# ModuleXuLyAmThanhPT2314.net
KiCad netlist of a schematic drawn in Altium Designer
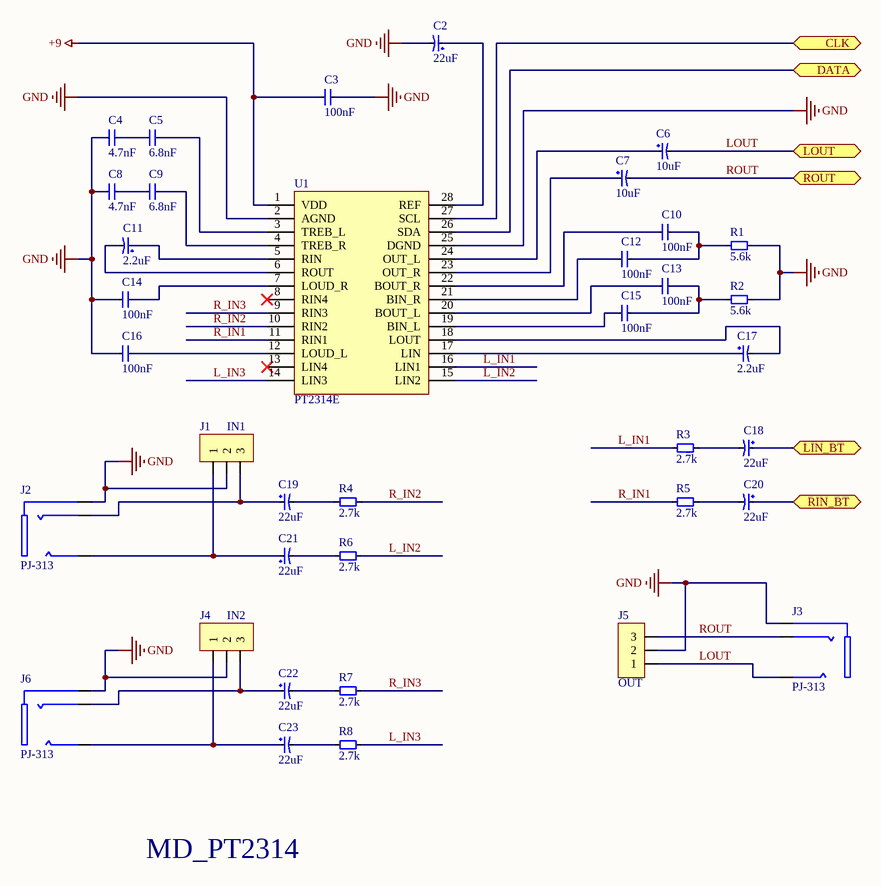
[diagram p0: ModuleXuLyAmThanhPT2314.SchDoc]

(export (version "E")
  (design (tool "Eeschema 10.0.6"))
  (components
    (comp (ref "C2")
      (value "22uF")
      (footprint "C-ELE-1.5-4X7MM")
      (description "Cac Loai Tu Hoa")
      (libsource (lib "phatvu1294_Lib") (part "CAP-ELE"))
    )
    (comp (ref "C3")
      (value "100nF")
      (footprint "C-0805")
      (description "Cac Loai Tu Khong Phan Cuc")
      (libsource (lib "phatvu1294_Lib") (part "CAP"))
    )
    (comp (ref "C4")
      (value "4.7nF")
      (footprint "C-0805")
      (description "Cac Loai Tu Khong Phan Cuc")
      (libsource (lib "phatvu1294_Lib") (part "CAP"))
    )
    (comp (ref "C5")
      (value "6.8nF")
      (footprint "C-0805")
      (description "Cac Loai Tu Khong Phan Cuc")
      (libsource (lib "phatvu1294_Lib") (part "CAP"))
    )
    (comp (ref "C6")
      (value "10uF")
      (footprint "C-ELE-1.5-4X7MM")
      (description "Cac Loai Tu Hoa")
      (libsource (lib "phatvu1294_Lib") (part "CAP-ELE"))
    )
    (comp (ref "C7")
      (value "10uF")
      (footprint "C-ELE-1.5-4X7MM")
      (description "Cac Loai Tu Hoa")
      (libsource (lib "phatvu1294_Lib") (part "CAP-ELE"))
    )
    (comp (ref "C8")
      (value "4.7nF")
      (footprint "C-0805")
      (description "Cac Loai Tu Khong Phan Cuc")
      (libsource (lib "phatvu1294_Lib") (part "CAP"))
    )
    (comp (ref "C9")
      (value "6.8nF")
      (footprint "C-0805")
      (description "Cac Loai Tu Khong Phan Cuc")
      (libsource (lib "phatvu1294_Lib") (part "CAP"))
    )
    (comp (ref "C10")
      (value "100nF")
      (footprint "C-0805")
      (description "Cac Loai Tu Khong Phan Cuc")
      (libsource (lib "phatvu1294_Lib") (part "CAP"))
    )
    (comp (ref "C11")
      (value "2.2uF")
      (footprint "C-ELE-1.5-4X7MM")
      (description "Cac Loai Tu Hoa")
      (libsource (lib "phatvu1294_Lib") (part "CAP-ELE"))
    )
    (comp (ref "C12")
      (value "100nF")
      (footprint "C-0805")
      (description "Cac Loai Tu Khong Phan Cuc")
      (libsource (lib "phatvu1294_Lib") (part "CAP"))
    )
    (comp (ref "C13")
      (value "100nF")
      (footprint "C-0805")
      (description "Cac Loai Tu Khong Phan Cuc")
      (libsource (lib "phatvu1294_Lib") (part "CAP"))
    )
    (comp (ref "C14")
      (value "100nF")
      (footprint "C-0805")
      (description "Cac Loai Tu Khong Phan Cuc")
      (libsource (lib "phatvu1294_Lib") (part "CAP"))
    )
    (comp (ref "C15")
      (value "100nF")
      (footprint "C-0805")
      (description "Cac Loai Tu Khong Phan Cuc")
      (libsource (lib "phatvu1294_Lib") (part "CAP"))
    )
    (comp (ref "C16")
      (value "100nF")
      (footprint "C-0805")
      (description "Cac Loai Tu Khong Phan Cuc")
      (libsource (lib "phatvu1294_Lib") (part "CAP"))
    )
    (comp (ref "C17")
      (value "2.2uF")
      (footprint "C-ELE-1.5-4X7MM")
      (description "Cac Loai Tu Hoa")
      (libsource (lib "phatvu1294_Lib") (part "CAP-ELE"))
    )
    (comp (ref "C18")
      (value "22uF")
      (footprint "C-ELE-1.5-4X7MM")
      (description "Cac Loai Tu Hoa")
      (libsource (lib "") (part "CAP-ELE_1"))
    )
    (comp (ref "C19")
      (value "22uF")
      (footprint "C-ELE-1.5-4X7MM")
      (description "Cac Loai Tu Hoa")
      (libsource (lib "phatvu1294_Lib") (part "CAP-ELE"))
    )
    (comp (ref "C20")
      (value "22uF")
      (footprint "C-ELE-1.5-4X7MM")
      (description "Cac Loai Tu Hoa")
      (libsource (lib "") (part "CAP-ELE_1"))
    )
    (comp (ref "C21")
      (value "22uF")
      (footprint "C-ELE-1.5-4X7MM")
      (description "Cac Loai Tu Hoa")
      (libsource (lib "") (part "CAP-ELE_1"))
    )
    (comp (ref "C22")
      (value "22uF")
      (footprint "C-ELE-1.5-4X7MM")
      (description "Cac Loai Tu Hoa")
      (libsource (lib "phatvu1294_Lib") (part "CAP-ELE"))
    )
    (comp (ref "C23")
      (value "22uF")
      (footprint "C-ELE-1.5-4X7MM")
      (description "Cac Loai Tu Hoa")
      (libsource (lib "phatvu1294_Lib") (part "CAP-ELE"))
    )
    (comp (ref "J1")
      (value "IN1")
      (footprint "XH1X3M-2.54")
      (description "Header 3 Chan XH 2.54mm")
      (libsource (lib "phatvu1294_Lib") (part "XH1X3-2.54"))
    )
    (comp (ref "J2")
      (value "PJ-313")
      (footprint "PJ-313")
      (description "Jack Ket Noi Audio 3.5MM")
      (libsource (lib "phatvu1294_Lib") (part "PJ-313"))
    )
    (comp (ref "J3")
      (value "PJ-313")
      (footprint "PJ-313")
      (description "Jack Ket Noi Audio 3.5MM")
      (libsource (lib "phatvu1294_Lib") (part "PJ-313"))
    )
    (comp (ref "J4")
      (value "IN2")
      (footprint "XH1X3M-2.54")
      (description "Header 3 Chan XH 2.54mm")
      (libsource (lib "phatvu1294_Lib") (part "XH1X3-2.54"))
    )
    (comp (ref "J5")
      (value "OUT")
      (footprint "XH1X3M-2.54")
      (description "Header 3 Chan XH 2.54mm")
      (libsource (lib "") (part "XH1X3-2.54_1"))
    )
    (comp (ref "J6")
      (value "PJ-313")
      (footprint "PJ-313")
      (description "Jack Ket Noi Audio 3.5MM")
      (libsource (lib "phatvu1294_Lib") (part "PJ-313"))
    )
    (comp (ref "R1")
      (value "5.6k")
      (footprint "R-0805")
      (description "Cac Loai Dien Tro")
      (libsource (lib "phatvu1294_Lib") (part "RES"))
    )
    (comp (ref "R2")
      (value "5.6k")
      (footprint "R-0805")
      (description "Cac Loai Dien Tro")
      (libsource (lib "phatvu1294_Lib") (part "RES"))
    )
    (comp (ref "R3")
      (value "2.7k")
      (footprint "R-0805")
      (description "Cac Loai Dien Tro")
      (libsource (lib "phatvu1294_Lib") (part "RES"))
    )
    (comp (ref "R4")
      (value "2.7k")
      (footprint "R-0805")
      (description "Cac Loai Dien Tro")
      (libsource (lib "phatvu1294_Lib") (part "RES"))
    )
    (comp (ref "R5")
      (value "2.7k")
      (footprint "R-0805")
      (description "Cac Loai Dien Tro")
      (libsource (lib "phatvu1294_Lib") (part "RES"))
    )
    (comp (ref "R6")
      (value "2.7k")
      (footprint "R-0805")
      (description "Cac Loai Dien Tro")
      (libsource (lib "phatvu1294_Lib") (part "RES"))
    )
    (comp (ref "R7")
      (value "2.7k")
      (footprint "R-0805")
      (description "Cac Loai Dien Tro")
      (libsource (lib "phatvu1294_Lib") (part "RES"))
    )
    (comp (ref "R8")
      (value "2.7k")
      (footprint "R-0805")
      (description "Cac Loai Dien Tro")
      (libsource (lib "phatvu1294_Lib") (part "RES"))
    )
    (comp (ref "U1")
      (value "PT2314E")
      (footprint "SO28W-1.27-300MIL")
      (description "IC Xu Ly Am Thanh So")
      (libsource (lib "phatvu1294_Lib") (part "PT2314E"))
    )
  )
  (nets
    (net (code "1") (name "+9") (class "Default")
      (node (ref "C3") (pin "1") (pinfunction "1_1") (pintype "passive"))
      (node (ref "U1") (pin "1") (pinfunction "VDD_1") (pintype "power_in"))
    )
    (net (code "2") (name "/CLK") (class "Default")
      (node (ref "U1") (pin "27") (pinfunction "SCL_27") (pintype "passive"))
    )
    (net (code "3") (name "/DATA") (class "Default")
      (node (ref "U1") (pin "26") (pinfunction "SDA_26") (pintype "passive"))
    )
    (net (code "4") (name "/LIN_BT") (class "Default")
      (node (ref "C18") (pin "1") (pinfunction "1_1") (pintype "passive"))
    )
    (net (code "5") (name "/LOUT") (class "Default")
      (node (ref "C6") (pin "2") (pinfunction "2_2") (pintype "passive"))
      (node (ref "J3") (pin "3") (pinfunction "3_3") (pintype "passive"))
      (node (ref "J5") (pin "1") (pinfunction "1_1") (pintype "passive"))
    )
    (net (code "6") (name "/L_IN1") (class "Default")
      (node (ref "R3") (pin "2") (pinfunction "2_2") (pintype "passive"))
      (node (ref "U1") (pin "16") (pinfunction "LIN1_16") (pintype "passive"))
    )
    (net (code "7") (name "/L_IN2") (class "Default")
      (node (ref "R6") (pin "2") (pinfunction "2_2") (pintype "passive"))
      (node (ref "U1") (pin "15") (pinfunction "LIN2_15") (pintype "passive"))
    )
    (net (code "8") (name "/L_IN3") (class "Default")
      (node (ref "R8") (pin "2") (pinfunction "2_2") (pintype "passive"))
      (node (ref "U1") (pin "14") (pinfunction "LIN3_14") (pintype "passive"))
    )
    (net (code "9") (name "/RIN_BT") (class "Default")
      (node (ref "C20") (pin "1") (pinfunction "1_1") (pintype "passive"))
    )
    (net (code "10") (name "/ROUT") (class "Default")
      (node (ref "C7") (pin "2") (pinfunction "2_2") (pintype "passive"))
      (node (ref "J3") (pin "2") (pinfunction "2_2") (pintype "passive"))
      (node (ref "J5") (pin "3") (pinfunction "3_3") (pintype "passive"))
    )
    (net (code "11") (name "/R_IN1") (class "Default")
      (node (ref "R5") (pin "1") (pinfunction "1_1") (pintype "passive"))
      (node (ref "U1") (pin "11") (pinfunction "RIN1_11") (pintype "passive"))
    )
    (net (code "12") (name "/R_IN2") (class "Default")
      (node (ref "R4") (pin "1") (pinfunction "1_1") (pintype "passive"))
      (node (ref "U1") (pin "10") (pinfunction "RIN2_10") (pintype "passive"))
    )
    (net (code "13") (name "/R_IN3") (class "Default")
      (node (ref "R7") (pin "1") (pinfunction "1_1") (pintype "passive"))
      (node (ref "U1") (pin "9") (pinfunction "RIN3_9") (pintype "passive"))
    )
    (net (code "14") (name "GND") (class "Default")
      (node (ref "C14") (pin "1") (pinfunction "1_1") (pintype "passive"))
      (node (ref "C16") (pin "1") (pinfunction "1_1") (pintype "passive"))
      (node (ref "C2") (pin "2") (pinfunction "2_2") (pintype "passive"))
      (node (ref "C3") (pin "2") (pinfunction "2_2") (pintype "passive"))
      (node (ref "C4") (pin "1") (pinfunction "1_1") (pintype "passive"))
      (node (ref "C8") (pin "1") (pinfunction "1_1") (pintype "passive"))
      (node (ref "J1") (pin "2") (pinfunction "2_2") (pintype "passive"))
      (node (ref "J2") (pin "1") (pinfunction "1_1") (pintype "passive"))
      (node (ref "J3") (pin "1") (pinfunction "1_1") (pintype "passive"))
      (node (ref "J4") (pin "2") (pinfunction "2_2") (pintype "passive"))
      (node (ref "J5") (pin "2") (pinfunction "2_2") (pintype "passive"))
      (node (ref "J6") (pin "1") (pinfunction "1_1") (pintype "passive"))
      (node (ref "R1") (pin "2") (pinfunction "2_2") (pintype "passive"))
      (node (ref "R2") (pin "2") (pinfunction "2_2") (pintype "passive"))
      (node (ref "U1") (pin "2") (pinfunction "AGND_2") (pintype "power_in"))
      (node (ref "U1") (pin "25") (pinfunction "DGND_25") (pintype "power_in"))
    )
    (net (code "15") (name "Net-(C4-Pad2)") (class "Default")
      (node (ref "C4") (pin "2") (pinfunction "2_2") (pintype "passive"))
      (node (ref "C5") (pin "1") (pinfunction "1_1") (pintype "passive"))
    )
    (net (code "16") (name "Net-(C8-Pad2)") (class "Default")
      (node (ref "C8") (pin "2") (pinfunction "2_2") (pintype "passive"))
      (node (ref "C9") (pin "1") (pinfunction "1_1") (pintype "passive"))
    )
    (net (code "17") (name "Net-(C10-Pad2)") (class "Default")
      (node (ref "C10") (pin "2") (pinfunction "2_2") (pintype "passive"))
      (node (ref "C12") (pin "2") (pinfunction "2_2") (pintype "passive"))
      (node (ref "R1") (pin "1") (pinfunction "1_1") (pintype "passive"))
    )
    (net (code "18") (name "Net-(C13-Pad2)") (class "Default")
      (node (ref "C13") (pin "2") (pinfunction "2_2") (pintype "passive"))
      (node (ref "C15") (pin "2") (pinfunction "2_2") (pintype "passive"))
      (node (ref "R2") (pin "1") (pinfunction "1_1") (pintype "passive"))
    )
    (net (code "19") (name "Net-(C18-Pad2)") (class "Default")
      (node (ref "C18") (pin "2") (pinfunction "2_2") (pintype "passive"))
      (node (ref "R3") (pin "1") (pinfunction "1_1") (pintype "passive"))
    )
    (net (code "20") (name "Net-(C19-Pad1)") (class "Default")
      (node (ref "C19") (pin "1") (pinfunction "1_1") (pintype "passive"))
      (node (ref "J1") (pin "3") (pinfunction "3_3") (pintype "passive"))
      (node (ref "J2") (pin "2") (pinfunction "2_2") (pintype "passive"))
    )
    (net (code "21") (name "Net-(C19-Pad2)") (class "Default")
      (node (ref "C19") (pin "2") (pinfunction "2_2") (pintype "passive"))
      (node (ref "R4") (pin "2") (pinfunction "2_2") (pintype "passive"))
    )
    (net (code "22") (name "Net-(C20-Pad2)") (class "Default")
      (node (ref "C20") (pin "2") (pinfunction "2_2") (pintype "passive"))
      (node (ref "R5") (pin "2") (pinfunction "2_2") (pintype "passive"))
    )
    (net (code "23") (name "Net-(C21-Pad1)") (class "Default")
      (node (ref "C21") (pin "1") (pinfunction "1_1") (pintype "passive"))
      (node (ref "J1") (pin "1") (pinfunction "1_1") (pintype "passive"))
      (node (ref "J2") (pin "3") (pinfunction "3_3") (pintype "passive"))
    )
    (net (code "24") (name "Net-(C21-Pad2)") (class "Default")
      (node (ref "C21") (pin "2") (pinfunction "2_2") (pintype "passive"))
      (node (ref "R6") (pin "1") (pinfunction "1_1") (pintype "passive"))
    )
    (net (code "25") (name "Net-(C22-Pad1)") (class "Default")
      (node (ref "C22") (pin "1") (pinfunction "1_1") (pintype "passive"))
      (node (ref "J4") (pin "3") (pinfunction "3_3") (pintype "passive"))
      (node (ref "J6") (pin "2") (pinfunction "2_2") (pintype "passive"))
    )
    (net (code "26") (name "Net-(C22-Pad2)") (class "Default")
      (node (ref "C22") (pin "2") (pinfunction "2_2") (pintype "passive"))
      (node (ref "R7") (pin "2") (pinfunction "2_2") (pintype "passive"))
    )
    (net (code "27") (name "Net-(C23-Pad1)") (class "Default")
      (node (ref "C23") (pin "1") (pinfunction "1_1") (pintype "passive"))
      (node (ref "J4") (pin "1") (pinfunction "1_1") (pintype "passive"))
      (node (ref "J6") (pin "3") (pinfunction "3_3") (pintype "passive"))
    )
    (net (code "28") (name "Net-(C23-Pad2)") (class "Default")
      (node (ref "C23") (pin "2") (pinfunction "2_2") (pintype "passive"))
      (node (ref "R8") (pin "1") (pinfunction "1_1") (pintype "passive"))
    )
    (net (code "29") (name "Net-(U1-BIN_L)") (class "Default")
      (node (ref "C15") (pin "1") (pinfunction "1_1") (pintype "passive"))
      (node (ref "U1") (pin "19") (pinfunction "BIN_L_19") (pintype "passive"))
    )
    (net (code "30") (name "Net-(U1-BIN_R)") (class "Default")
      (node (ref "C12") (pin "1") (pinfunction "1_1") (pintype "passive"))
      (node (ref "U1") (pin "21") (pinfunction "BIN_R_21") (pintype "passive"))
    )
    (net (code "31") (name "Net-(U1-BOUT_L)") (class "Default")
      (node (ref "C13") (pin "1") (pinfunction "1_1") (pintype "passive"))
      (node (ref "U1") (pin "20") (pinfunction "BOUT_L_20") (pintype "passive"))
    )
    (net (code "32") (name "Net-(U1-BOUT_R)") (class "Default")
      (node (ref "C10") (pin "1") (pinfunction "1_1") (pintype "passive"))
      (node (ref "U1") (pin "22") (pinfunction "BOUT_R_22") (pintype "passive"))
    )
    (net (code "33") (name "Net-(U1-LIN)") (class "Default")
      (node (ref "C17") (pin "1") (pinfunction "1_1") (pintype "passive"))
      (node (ref "U1") (pin "17") (pinfunction "LIN_17") (pintype "passive"))
    )
    (net (code "34") (name "Net-(U1-LOUD_L)") (class "Default")
      (node (ref "C16") (pin "2") (pinfunction "2_2") (pintype "passive"))
      (node (ref "U1") (pin "12") (pinfunction "LOUD_L_12") (pintype "passive"))
    )
    (net (code "35") (name "Net-(U1-LOUD_R)") (class "Default")
      (node (ref "C14") (pin "2") (pinfunction "2_2") (pintype "passive"))
      (node (ref "U1") (pin "7") (pinfunction "LOUD_R_7") (pintype "passive"))
    )
    (net (code "36") (name "Net-(U1-LOUT)") (class "Default")
      (node (ref "C17") (pin "2") (pinfunction "2_2") (pintype "passive"))
      (node (ref "U1") (pin "18") (pinfunction "LOUT_18") (pintype "passive"))
    )
    (net (code "37") (name "Net-(U1-OUT_L)") (class "Default")
      (node (ref "C6") (pin "1") (pinfunction "1_1") (pintype "passive"))
      (node (ref "U1") (pin "24") (pinfunction "OUT_L_24") (pintype "passive"))
    )
    (net (code "38") (name "Net-(U1-OUT_R)") (class "Default")
      (node (ref "C7") (pin "1") (pinfunction "1_1") (pintype "passive"))
      (node (ref "U1") (pin "23") (pinfunction "OUT_R_23") (pintype "passive"))
    )
    (net (code "39") (name "Net-(U1-REF)") (class "Default")
      (node (ref "C2") (pin "1") (pinfunction "1_1") (pintype "passive"))
      (node (ref "U1") (pin "28") (pinfunction "REF_28") (pintype "passive"))
    )
    (net (code "40") (name "Net-(U1-RIN)") (class "Default")
      (node (ref "C11") (pin "1") (pinfunction "1_1") (pintype "passive"))
      (node (ref "U1") (pin "5") (pinfunction "RIN_5") (pintype "passive"))
    )
    (net (code "41") (name "Net-(U1-ROUT)") (class "Default")
      (node (ref "C11") (pin "2") (pinfunction "2_2") (pintype "passive"))
      (node (ref "U1") (pin "6") (pinfunction "ROUT_6") (pintype "passive"))
    )
    (net (code "42") (name "Net-(U1-TREB_L)") (class "Default")
      (node (ref "C5") (pin "2") (pinfunction "2_2") (pintype "passive"))
      (node (ref "U1") (pin "3") (pinfunction "TREB_L_3") (pintype "passive"))
    )
    (net (code "43") (name "Net-(U1-TREB_R)") (class "Default")
      (node (ref "C9") (pin "2") (pinfunction "2_2") (pintype "passive"))
      (node (ref "U1") (pin "4") (pinfunction "TREB_R_4") (pintype "passive"))
    )
    (net (code "44") (name "unconnected-(U1-LIN4-Pad13)") (class "Default")
      (node (ref "U1") (pin "13") (pinfunction "LIN4_13") (pintype "passive+no_connect"))
    )
    (net (code "45") (name "unconnected-(U1-RIN4-Pad8)") (class "Default")
      (node (ref "U1") (pin "8") (pinfunction "RIN4_8") (pintype "passive+no_connect"))
    )
  )
)
